# M617C.net
KiCad netlist of a schematic drawn in EAGLE
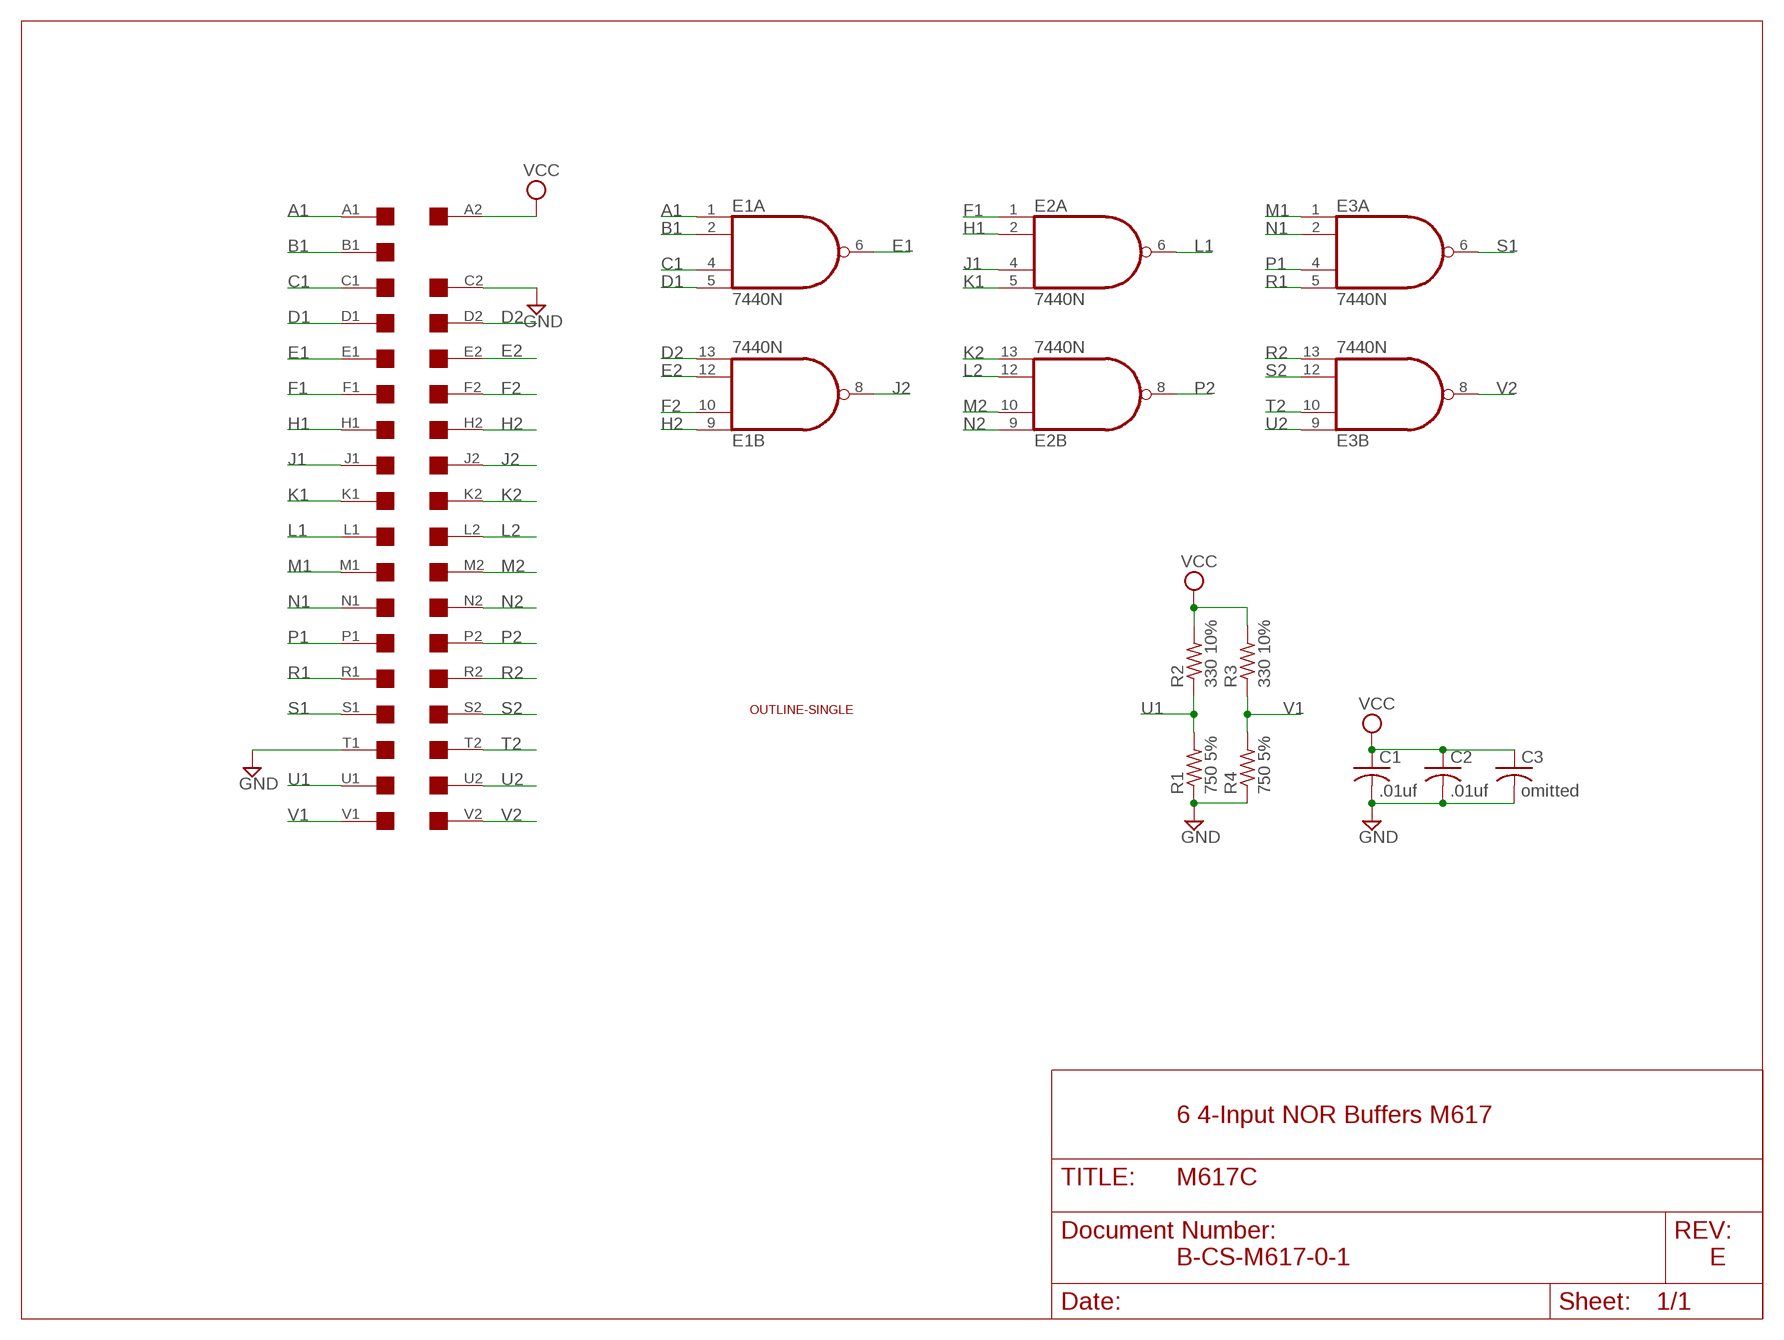
[diagram p0: schematic, sheet 1]

(export (version "E")
  (design (tool "Eeschema 10.0.6"))
  (components
    (comp (ref "C1")
      (value ".01uf")
      (footprint "eagle-import:C050-025X075")
      (libsource (lib "eagle-import") (part "C-US050-025X075"))
    )
    (comp (ref "C2")
      (value ".01uf")
      (footprint "eagle-import:C050-025X075")
      (libsource (lib "eagle-import") (part "C-US050-025X075"))
    )
    (comp (ref "C3")
      (value "omitted")
      (footprint "eagle-import:C050-025X075")
      (libsource (lib "eagle-import") (part "C-US050-025X075"))
    )
    (comp (ref "E1")
      (value "7440N")
      (footprint "eagle-import:DIL14")
      (libsource (lib "eagle-import") (part "7420NS"))
    )
    (comp (ref "E2")
      (value "7440N")
      (footprint "eagle-import:DIL14")
      (libsource (lib "eagle-import") (part "7420NS"))
    )
    (comp (ref "E3")
      (value "7440N")
      (footprint "eagle-import:DIL14")
      (libsource (lib "eagle-import") (part "7420NS"))
    )
    (comp (ref "R1")
      (value "750 5%")
      (footprint "eagle-import:0207_10")
      (libsource (lib "eagle-import") (part "R-US_0207/10"))
    )
    (comp (ref "R2")
      (value "330 10%")
      (footprint "eagle-import:0207_10")
      (libsource (lib "eagle-import") (part "R-US_0207/10"))
    )
    (comp (ref "R3")
      (value "330 10%")
      (footprint "eagle-import:0207_10")
      (libsource (lib "eagle-import") (part "R-US_0207/10"))
    )
    (comp (ref "R4")
      (value "750 5%")
      (footprint "eagle-import:0207_10")
      (libsource (lib "eagle-import") (part "R-US_0207/10"))
    )
    (comp (ref "U$1")
      (value "SINGLE")
      (footprint "eagle-import:EDGE-CON2")
      (libsource (lib "eagle-import") (part "SINGLE"))
    )
    (comp (ref "U$4")
      (value "OUTLINE-SINGLE")
      (footprint "eagle-import:SINGLE")
      (libsource (lib "eagle-import") (part "OUTLINE-SINGLE"))
    )
  )
  (nets
    (net (code "1") (name "/A1") (class "Default")
      (node (ref "E1") (pin "1") (pinfunction "I0_1") (pintype "input"))
      (node (ref "U$1") (pin "A1") (pinfunction "1_A1") (pintype "bidirectional"))
    )
    (net (code "2") (name "/B1") (class "Default")
      (node (ref "E1") (pin "2") (pinfunction "I1_2") (pintype "input"))
      (node (ref "U$1") (pin "B1") (pinfunction "1_B1") (pintype "bidirectional"))
    )
    (net (code "3") (name "/C1") (class "Default")
      (node (ref "E1") (pin "4") (pinfunction "I2_4") (pintype "input"))
      (node (ref "U$1") (pin "C1") (pinfunction "1_C1") (pintype "bidirectional"))
    )
    (net (code "4") (name "/D1") (class "Default")
      (node (ref "E1") (pin "5") (pinfunction "I3_5") (pintype "input"))
      (node (ref "U$1") (pin "D1") (pinfunction "1_D1") (pintype "bidirectional"))
    )
    (net (code "5") (name "/D2") (class "Default")
      (node (ref "E1") (pin "13") (pinfunction "I3_13") (pintype "input"))
      (node (ref "U$1") (pin "D2") (pinfunction "1_D2") (pintype "bidirectional"))
    )
    (net (code "6") (name "/E1") (class "Default")
      (node (ref "E1") (pin "6") (pinfunction "O_6") (pintype "output"))
      (node (ref "U$1") (pin "E1") (pinfunction "1_E1") (pintype "bidirectional"))
    )
    (net (code "7") (name "/E2") (class "Default")
      (node (ref "E1") (pin "12") (pinfunction "I2_12") (pintype "input"))
      (node (ref "U$1") (pin "E2") (pinfunction "1_E2") (pintype "bidirectional"))
    )
    (net (code "8") (name "/F1") (class "Default")
      (node (ref "E2") (pin "1") (pinfunction "I0_1") (pintype "input"))
      (node (ref "U$1") (pin "F1") (pinfunction "1_F1") (pintype "bidirectional"))
    )
    (net (code "9") (name "/F2") (class "Default")
      (node (ref "E1") (pin "10") (pinfunction "I1_10") (pintype "input"))
      (node (ref "U$1") (pin "F2") (pinfunction "1_F2") (pintype "bidirectional"))
    )
    (net (code "10") (name "/H1") (class "Default")
      (node (ref "E2") (pin "2") (pinfunction "I1_2") (pintype "input"))
      (node (ref "U$1") (pin "H1") (pinfunction "1_H1") (pintype "bidirectional"))
    )
    (net (code "11") (name "/H2") (class "Default")
      (node (ref "E1") (pin "9") (pinfunction "I0_9") (pintype "input"))
      (node (ref "U$1") (pin "H2") (pinfunction "1_H2") (pintype "bidirectional"))
    )
    (net (code "12") (name "/J1") (class "Default")
      (node (ref "E2") (pin "4") (pinfunction "I2_4") (pintype "input"))
      (node (ref "U$1") (pin "J1") (pinfunction "1_J1") (pintype "bidirectional"))
    )
    (net (code "13") (name "/J2") (class "Default")
      (node (ref "E1") (pin "8") (pinfunction "O_8") (pintype "output"))
      (node (ref "U$1") (pin "J2") (pinfunction "1_J2") (pintype "bidirectional"))
    )
    (net (code "14") (name "/K1") (class "Default")
      (node (ref "E2") (pin "5") (pinfunction "I3_5") (pintype "input"))
      (node (ref "U$1") (pin "K1") (pinfunction "1_K1") (pintype "bidirectional"))
    )
    (net (code "15") (name "/K2") (class "Default")
      (node (ref "E2") (pin "13") (pinfunction "I3_13") (pintype "input"))
      (node (ref "U$1") (pin "K2") (pinfunction "1_K2") (pintype "bidirectional"))
    )
    (net (code "16") (name "/L1") (class "Default")
      (node (ref "E2") (pin "6") (pinfunction "O_6") (pintype "output"))
      (node (ref "U$1") (pin "L1") (pinfunction "1_L1") (pintype "bidirectional"))
    )
    (net (code "17") (name "/L2") (class "Default")
      (node (ref "E2") (pin "12") (pinfunction "I2_12") (pintype "input"))
      (node (ref "U$1") (pin "L2") (pinfunction "1_L2") (pintype "bidirectional"))
    )
    (net (code "18") (name "/M1") (class "Default")
      (node (ref "E3") (pin "1") (pinfunction "I0_1") (pintype "input"))
      (node (ref "U$1") (pin "M1") (pinfunction "1_M1") (pintype "bidirectional"))
    )
    (net (code "19") (name "/M2") (class "Default")
      (node (ref "E2") (pin "10") (pinfunction "I1_10") (pintype "input"))
      (node (ref "U$1") (pin "M2") (pinfunction "1_M2") (pintype "bidirectional"))
    )
    (net (code "20") (name "/N1") (class "Default")
      (node (ref "E3") (pin "2") (pinfunction "I1_2") (pintype "input"))
      (node (ref "U$1") (pin "N1") (pinfunction "1_N1") (pintype "bidirectional"))
    )
    (net (code "21") (name "/N2") (class "Default")
      (node (ref "E2") (pin "9") (pinfunction "I0_9") (pintype "input"))
      (node (ref "U$1") (pin "N2") (pinfunction "1_N2") (pintype "bidirectional"))
    )
    (net (code "22") (name "/P1") (class "Default")
      (node (ref "E3") (pin "4") (pinfunction "I2_4") (pintype "input"))
      (node (ref "U$1") (pin "P1") (pinfunction "1_P1") (pintype "bidirectional"))
    )
    (net (code "23") (name "/P2") (class "Default")
      (node (ref "E2") (pin "8") (pinfunction "O_8") (pintype "output"))
      (node (ref "U$1") (pin "P2") (pinfunction "1_P2") (pintype "bidirectional"))
    )
    (net (code "24") (name "/R1") (class "Default")
      (node (ref "E3") (pin "5") (pinfunction "I3_5") (pintype "input"))
      (node (ref "U$1") (pin "R1") (pinfunction "1_R1") (pintype "bidirectional"))
    )
    (net (code "25") (name "/R2") (class "Default")
      (node (ref "E3") (pin "13") (pinfunction "I3_13") (pintype "input"))
      (node (ref "U$1") (pin "R2") (pinfunction "1_R2") (pintype "bidirectional"))
    )
    (net (code "26") (name "/S1") (class "Default")
      (node (ref "E3") (pin "6") (pinfunction "O_6") (pintype "output"))
      (node (ref "U$1") (pin "S1") (pinfunction "1_S1") (pintype "bidirectional"))
    )
    (net (code "27") (name "/S2") (class "Default")
      (node (ref "E3") (pin "12") (pinfunction "I2_12") (pintype "input"))
      (node (ref "U$1") (pin "S2") (pinfunction "1_S2") (pintype "bidirectional"))
    )
    (net (code "28") (name "/T2") (class "Default")
      (node (ref "E3") (pin "10") (pinfunction "I1_10") (pintype "input"))
      (node (ref "U$1") (pin "T2") (pinfunction "1_T2") (pintype "bidirectional"))
    )
    (net (code "29") (name "/U1") (class "Default")
      (node (ref "R1") (pin "2") (pinfunction "2_2") (pintype "passive"))
      (node (ref "R2") (pin "1") (pinfunction "1_1") (pintype "passive"))
      (node (ref "U$1") (pin "U1") (pinfunction "1_U1") (pintype "bidirectional"))
    )
    (net (code "30") (name "/U2") (class "Default")
      (node (ref "E3") (pin "9") (pinfunction "I0_9") (pintype "input"))
      (node (ref "U$1") (pin "U2") (pinfunction "1_U2") (pintype "bidirectional"))
    )
    (net (code "31") (name "/V1") (class "Default")
      (node (ref "R3") (pin "1") (pinfunction "1_1") (pintype "passive"))
      (node (ref "R4") (pin "2") (pinfunction "2_2") (pintype "passive"))
      (node (ref "U$1") (pin "V1") (pinfunction "1_V1") (pintype "bidirectional"))
    )
    (net (code "32") (name "/V2") (class "Default")
      (node (ref "E3") (pin "8") (pinfunction "O_8") (pintype "output"))
      (node (ref "U$1") (pin "V2") (pinfunction "1_V2") (pintype "bidirectional"))
    )
    (net (code "33") (name "GND") (class "Default")
      (node (ref "C1") (pin "2") (pinfunction "2_2") (pintype "passive"))
      (node (ref "C2") (pin "2") (pinfunction "2_2") (pintype "passive"))
      (node (ref "C3") (pin "2") (pinfunction "2_2") (pintype "passive"))
      (node (ref "R1") (pin "1") (pinfunction "1_1") (pintype "passive"))
      (node (ref "R4") (pin "1") (pinfunction "1_1") (pintype "passive"))
      (node (ref "U$1") (pin "C2") (pinfunction "1_C2") (pintype "bidirectional"))
      (node (ref "U$1") (pin "T1") (pinfunction "1_T1") (pintype "bidirectional"))
    )
    (net (code "34") (name "VCC") (class "Default")
      (node (ref "C1") (pin "1") (pinfunction "1_1") (pintype "passive"))
      (node (ref "C2") (pin "1") (pinfunction "1_1") (pintype "passive"))
      (node (ref "C3") (pin "1") (pinfunction "1_1") (pintype "passive"))
      (node (ref "R2") (pin "2") (pinfunction "2_2") (pintype "passive"))
      (node (ref "R3") (pin "2") (pinfunction "2_2") (pintype "passive"))
      (node (ref "U$1") (pin "A2") (pinfunction "1_A2") (pintype "bidirectional"))
    )
  )
)
